# connectors.net
KiCad netlist of a schematic drawn in Altium Designer
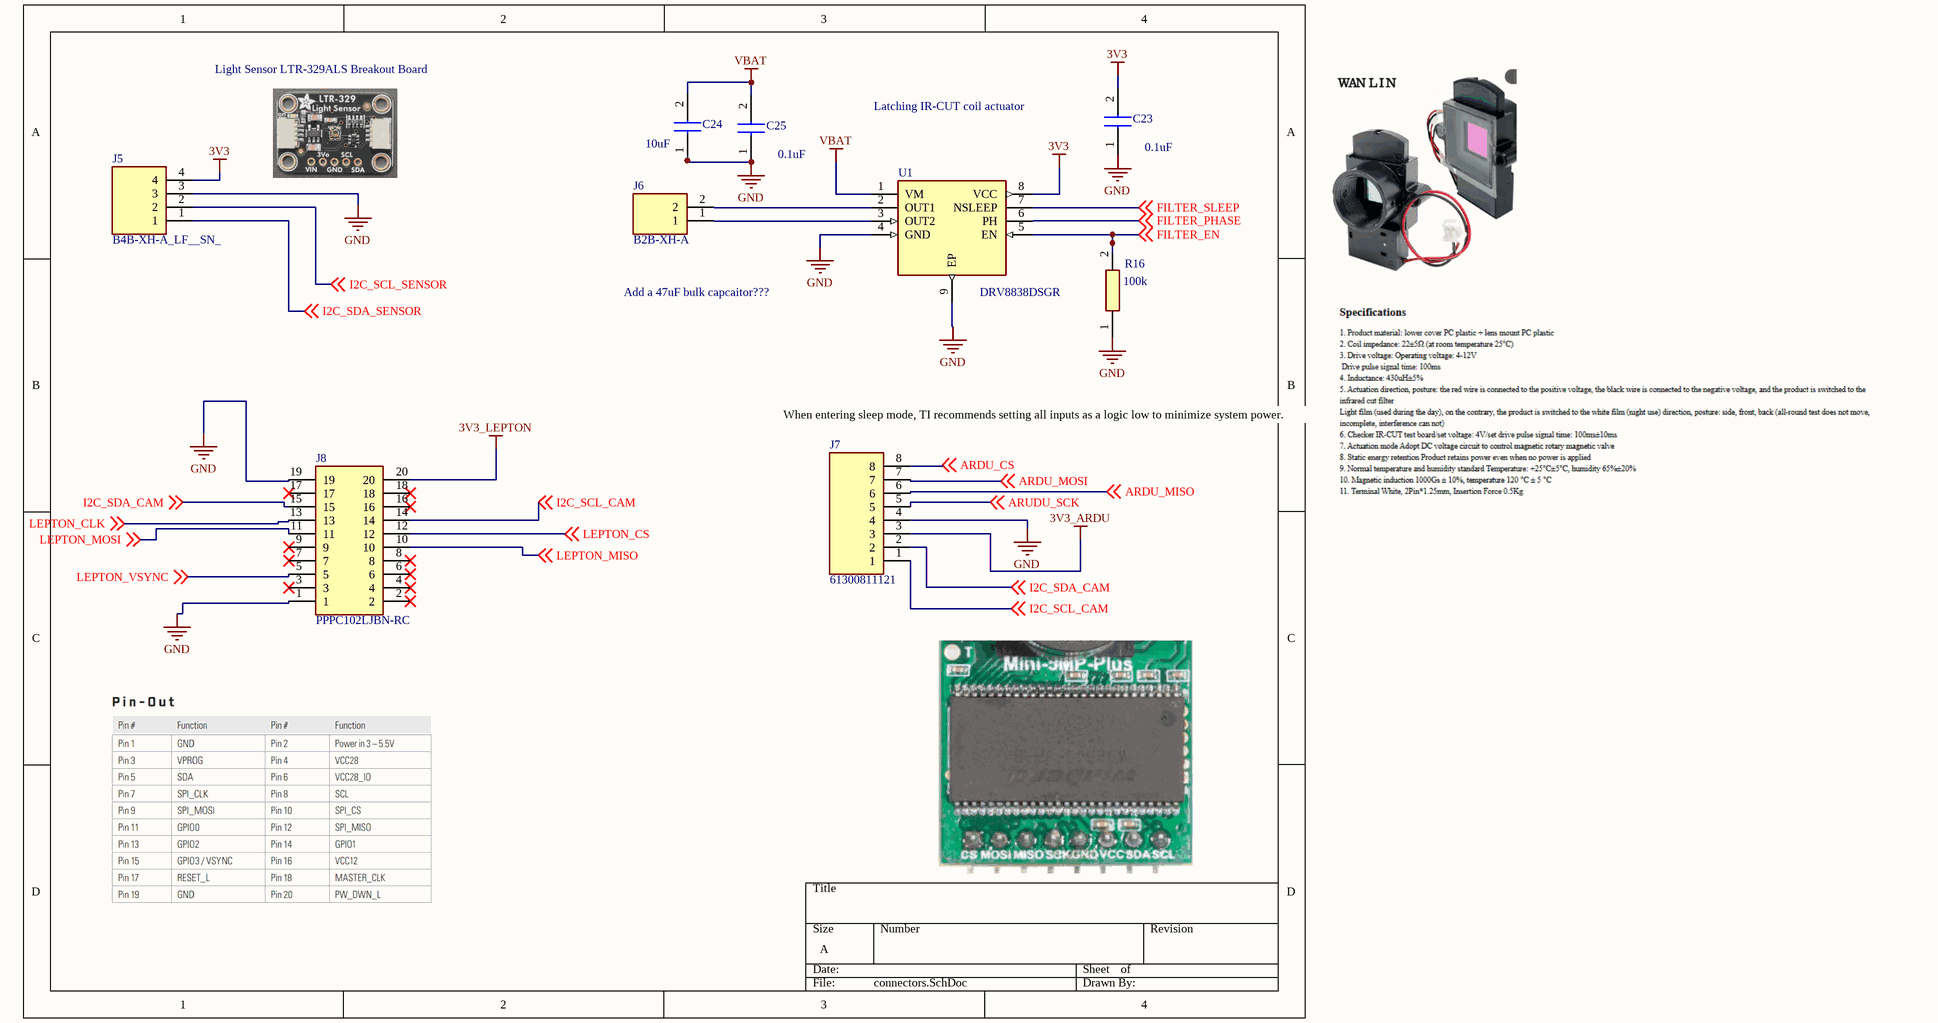
[diagram p0: connectors.SchDoc]

(export (version "E")
  (design (tool "Eeschema 10.0.6"))
  (components
    (comp (ref "C23")
      (value "0.1uF")
      (footprint "SamacSys:CAPC1608X90N")
      (description "0603 CAP X5R 25V")
      (fields
        (field (name "MANUFACTURER_PART_NUMBER") "CC0603KRX7R0BB104")
        (field (name "MOUSER PART NUMBER") "603-CC603KRX7R0BB104")
      )
      (libsource (lib "*") (part "CC0603KRX7R0BB104"))
    )
    (comp (ref "C24")
      (value "10uF")
      (footprint "SamacSys:CAPC1608X90N")
      (description "0603 CAP X5R 25V")
      (fields
        (field (name "MANUFACTURER_PART_NUMBER") "CC0603KRX7R0BB104")
        (field (name "MOUSER PART NUMBER") "603-CC603KRX7R0BB104")
      )
      (libsource (lib "*") (part "CC0603KRX7R0BB104"))
    )
    (comp (ref "C25")
      (value "0.1uF")
      (footprint "SamacSys:CAPC1608X90N")
      (description "0603 CAP X5R 25V")
      (fields
        (field (name "MANUFACTURER_PART_NUMBER") "CC0603KRX7R0BB104")
        (field (name "MOUSER PART NUMBER") "603-CC603KRX7R0BB104")
      )
      (libsource (lib "*") (part "CC0603KRX7R0BB104"))
    )
    (comp (ref "J5")
      (value "B4B-XH-A_LF__SN_")
      (footprint "SamacSys:B4BXHALFSN")
      (description "Connector")
      (fields
        (field (name "MANUFACTURER_PART_NUMBER") "B4B-XH-A(LF)(SN)")
        (field (name "MOUSER PART NUMBER") "306-B4BXHALFSN")
      )
      (libsource (lib "*") (part "B4B-XH-A_LF__SN_"))
    )
    (comp (ref "J6")
      (value "B2B-XH-A")
      (footprint "SamacSys:SHDR2W64P0X250_1X2_740X575X700P")
      (description "Connector")
      (libsource (lib "*") (part "B2B-XH-A"))
    )
    (comp (ref "J7")
      (value "61300811121")
      (footprint "SamacSys:HDRV8W64P0X254_1X8_2032X254X854P")
      (description "Connector")
      (fields (field (name "MOUSER PART NUMBER") "710-61300811121"))
      (libsource (lib "*") (part "61300811121"))
    )
    (comp (ref "J8")
      (value "PPPC102LJBN-RC")
      (footprint "SamacSys:RHDRRA20W60P254X254_2X10_2590X508X850P")
      (description "Connector")
      (libsource (lib "*") (part "PPPC102LJBN-RC"))
    )
    (comp (ref "R16")
      (value "100k")
      (footprint "SamacSys:RESC1608X55N")
      (description "Resistor SMD 0603 1% 0.1W")
      (fields (field (name "MANUFACTURER_PART_NUMBER") "RC0603FR0710KL"))
      (libsource (lib "*") (part "RC0603FR0710KL"))
    )
    (comp (ref "U1")
      (value "DRV8838DSGR")
      (footprint "SamacSys:SON50P200X200X80-9N")
      (description "Undefined or Miscellaneous")
      (fields (field (name "MOUSER PART NUMBER") "595-DRV8838DSGR"))
      (libsource (lib "SamacSys") (part "DRV8838DSGR"))
    )
  )
  (nets
    (net (code "1") (name "3V3") (class "Default")
      (node (ref "C23") (pin "2") (pinfunction "2_2") (pintype "passive"))
      (node (ref "J5") (pin "4") (pinfunction "4_4") (pintype "passive"))
      (node (ref "U1") (pin "8") (pinfunction "VCC_8") (pintype "output"))
    )
    (net (code "2") (name "3V3_ARDU") (class "Default")
      (node (ref "J7") (pin "3") (pinfunction "3_3") (pintype "passive"))
    )
    (net (code "3") (name "3V3_LEPTON") (class "Default")
      (node (ref "J8") (pin "20") (pinfunction "20_20") (pintype "passive"))
    )
    (net (code "4") (name "ARDU_CS") (class "Default")
      (node (ref "J7") (pin "8") (pinfunction "8_8") (pintype "passive"))
    )
    (net (code "5") (name "ARDU_MISO") (class "Default")
      (node (ref "J7") (pin "6") (pinfunction "6_6") (pintype "passive"))
    )
    (net (code "6") (name "ARDU_MOSI") (class "Default")
      (node (ref "J7") (pin "7") (pinfunction "7_7") (pintype "passive"))
    )
    (net (code "7") (name "ARUDU_SCK") (class "Default")
      (node (ref "J7") (pin "5") (pinfunction "5_5") (pintype "passive"))
    )
    (net (code "8") (name "FILTER_EN") (class "Default")
      (node (ref "R16") (pin "2") (pinfunction "2_2") (pintype "passive"))
      (node (ref "U1") (pin "5") (pinfunction "EN_5") (pintype "input"))
    )
    (net (code "9") (name "FILTER_PHASE") (class "Default")
      (node (ref "U1") (pin "6") (pinfunction "PH_6") (pintype "power_in"))
    )
    (net (code "10") (name "FILTER_SLEEP") (class "Default")
      (node (ref "U1") (pin "7") (pinfunction "NSLEEP_7") (pintype "power_in"))
    )
    (net (code "11") (name "GND") (class "Default")
      (node (ref "C23") (pin "1") (pinfunction "1_1") (pintype "passive"))
      (node (ref "C24") (pin "1") (pinfunction "1_1") (pintype "passive"))
      (node (ref "C25") (pin "1") (pinfunction "1_1") (pintype "passive"))
      (node (ref "J5") (pin "3") (pinfunction "3_3") (pintype "passive"))
      (node (ref "J7") (pin "4") (pinfunction "4_4") (pintype "passive"))
      (node (ref "J8") (pin "1") (pinfunction "1_1") (pintype "passive"))
      (node (ref "J8") (pin "19") (pinfunction "19_19") (pintype "passive"))
      (node (ref "R16") (pin "1") (pinfunction "1_1") (pintype "passive"))
      (node (ref "U1") (pin "4") (pinfunction "GND_4") (pintype "input"))
      (node (ref "U1") (pin "9") (pinfunction "EP_9") (pintype "output"))
    )
    (net (code "12") (name "I2C_SCL_CAM") (class "Default")
      (node (ref "J7") (pin "1") (pinfunction "1_1") (pintype "passive"))
      (node (ref "J8") (pin "14") (pinfunction "14_14") (pintype "passive"))
    )
    (net (code "13") (name "I2C_SCL_SENSOR") (class "Default")
      (node (ref "J5") (pin "2") (pinfunction "2_2") (pintype "passive"))
    )
    (net (code "14") (name "I2C_SDA_CAM") (class "Default")
      (node (ref "J7") (pin "2") (pinfunction "2_2") (pintype "passive"))
      (node (ref "J8") (pin "15") (pinfunction "15_15") (pintype "passive"))
    )
    (net (code "15") (name "I2C_SDA_SENSOR") (class "Default")
      (node (ref "J5") (pin "1") (pinfunction "1_1") (pintype "passive"))
    )
    (net (code "16") (name "LEPTON_CLK") (class "Default")
      (node (ref "J8") (pin "13") (pinfunction "13_13") (pintype "passive"))
    )
    (net (code "17") (name "LEPTON_CS") (class "Default")
      (node (ref "J8") (pin "12") (pinfunction "12_12") (pintype "passive"))
    )
    (net (code "18") (name "LEPTON_MISO") (class "Default")
      (node (ref "J8") (pin "10") (pinfunction "10_10") (pintype "passive"))
    )
    (net (code "19") (name "LEPTON_MOSI") (class "Default")
      (node (ref "J8") (pin "11") (pinfunction "11_11") (pintype "passive"))
    )
    (net (code "20") (name "LEPTON_VSYNC") (class "Default")
      (node (ref "J8") (pin "5") (pinfunction "5_5") (pintype "passive"))
    )
    (net (code "21") (name "Net-(U1-OUT1)") (class "Default")
      (node (ref "J6") (pin "2") (pinfunction "2_2") (pintype "passive"))
      (node (ref "U1") (pin "2") (pinfunction "OUT1_2") (pintype "power_in"))
    )
    (net (code "22") (name "Net-(U1-OUT2)") (class "Default")
      (node (ref "J6") (pin "1") (pinfunction "1_1") (pintype "passive"))
      (node (ref "U1") (pin "3") (pinfunction "OUT2_3") (pintype "input"))
    )
    (net (code "23") (name "VBAT") (class "Default")
      (node (ref "C24") (pin "2") (pinfunction "2_2") (pintype "passive"))
      (node (ref "C25") (pin "2") (pinfunction "2_2") (pintype "passive"))
      (node (ref "U1") (pin "1") (pinfunction "VM_1") (pintype "power_in"))
    )
    (net (code "24") (name "unconnected-(J8-Pad2)") (class "Default")
      (node (ref "J8") (pin "2") (pinfunction "2_2") (pintype "passive+no_connect"))
    )
    (net (code "25") (name "unconnected-(J8-Pad3)") (class "Default")
      (node (ref "J8") (pin "3") (pinfunction "3_3") (pintype "passive+no_connect"))
    )
    (net (code "26") (name "unconnected-(J8-Pad4)") (class "Default")
      (node (ref "J8") (pin "4") (pinfunction "4_4") (pintype "passive+no_connect"))
    )
    (net (code "27") (name "unconnected-(J8-Pad6)") (class "Default")
      (node (ref "J8") (pin "6") (pinfunction "6_6") (pintype "passive+no_connect"))
    )
    (net (code "28") (name "unconnected-(J8-Pad7)") (class "Default")
      (node (ref "J8") (pin "7") (pinfunction "7_7") (pintype "passive+no_connect"))
    )
    (net (code "29") (name "unconnected-(J8-Pad8)") (class "Default")
      (node (ref "J8") (pin "8") (pinfunction "8_8") (pintype "passive+no_connect"))
    )
    (net (code "30") (name "unconnected-(J8-Pad9)") (class "Default")
      (node (ref "J8") (pin "9") (pinfunction "9_9") (pintype "passive+no_connect"))
    )
    (net (code "31") (name "unconnected-(J8-Pad16)") (class "Default")
      (node (ref "J8") (pin "16") (pinfunction "16_16") (pintype "passive+no_connect"))
    )
    (net (code "32") (name "unconnected-(J8-Pad17)") (class "Default")
      (node (ref "J8") (pin "17") (pinfunction "17_17") (pintype "passive+no_connect"))
    )
    (net (code "33") (name "unconnected-(J8-Pad18)") (class "Default")
      (node (ref "J8") (pin "18") (pinfunction "18_18") (pintype "passive+no_connect"))
    )
  )
)
